# CAN.net
KiCad netlist of a schematic drawn in Altium Designer
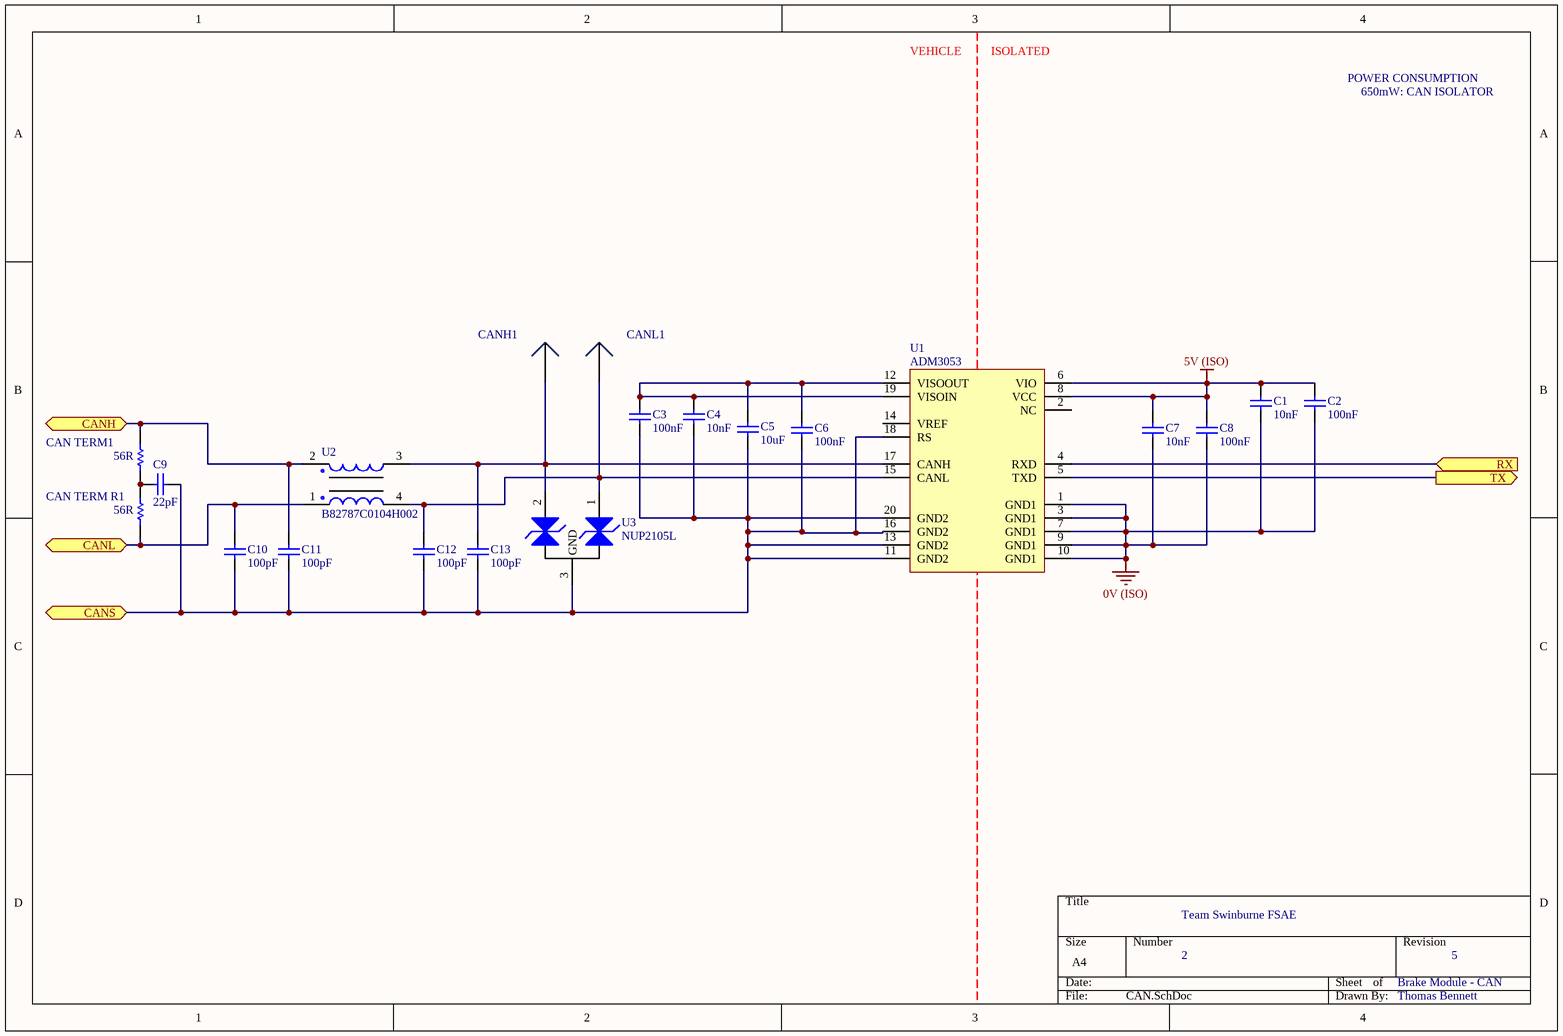
[diagram p0: CAN.SchDoc]

(export (version "E")
  (design (tool "Eeschema 10.0.6"))
  (components
    (comp (ref "C1")
      (value "10nF")
      (footprint "C0603")
      (fields (field (name "PART NUMBER") "CC0603JPX7R9BB103") (field (name "TOLERANCE") "5%"))
      (libsource (lib "AMS_Component_Library") (part "Capacitor"))
    )
    (comp (ref "C2")
      (value "100nF")
      (footprint "C0603")
      (fields (field (name "PART NUMBER") "CC0603ZPY5V9BB104") (field (name "TOLERANCE") "5%"))
      (libsource (lib "AMS_Component_Library") (part "Capacitor"))
    )
    (comp (ref "C3")
      (value "100nF")
      (footprint "C0603")
      (fields (field (name "PART NUMBER") "CC0603ZPY5V9BB104") (field (name "TOLERANCE") "5%"))
      (libsource (lib "AMS_Component_Library") (part "Capacitor"))
    )
    (comp (ref "C4")
      (value "10nF")
      (footprint "C0603")
      (fields (field (name "PART NUMBER") "CC0603JPX7R9BB103") (field (name "TOLERANCE") "5%"))
      (libsource (lib "AMS_Component_Library") (part "Capacitor"))
    )
    (comp (ref "C5")
      (value "10uF")
      (footprint "C0603")
      (fields (field (name "PART NUMBER") "GRM188R6YA106MA73D") (field (name "TOLERANCE") "20%"))
      (libsource (lib "AMS_Component_Library") (part "Capacitor"))
    )
    (comp (ref "C6")
      (value "100nF")
      (footprint "C0603")
      (fields (field (name "PART NUMBER") "CC0603ZPY5V9BB104") (field (name "TOLERANCE") "5%"))
      (libsource (lib "AMS_Component_Library") (part "Capacitor"))
    )
    (comp (ref "C7")
      (value "10nF")
      (footprint "C0603")
      (fields (field (name "PART NUMBER") "CC0603JPX7R9BB103") (field (name "TOLERANCE") "5%"))
      (libsource (lib "AMS_Component_Library") (part "Capacitor"))
    )
    (comp (ref "C8")
      (value "100nF")
      (footprint "C0603")
      (fields (field (name "PART NUMBER") "CC0603ZPY5V9BB104") (field (name "TOLERANCE") "5%"))
      (libsource (lib "AMS_Component_Library") (part "Capacitor"))
    )
    (comp (ref "C9")
      (value "22pF")
      (footprint "0805")
      (fields
        (field (name "PART NUMBER") "GRM21A5C2E220JW01D")
        (field (name "TOLERANCE") "±5%")
        (field (name "MANUFACTURER") "muRata")
      )
      (libsource (lib "ts_20-standard-library") (part "Capacitor"))
    )
    (comp (ref "C10")
      (value "100pF")
      (footprint "C0603")
      (fields (field (name "PART NUMBER") "CC0603JPNPO9BN101") (field (name "TOLERANCE") "5%"))
      (libsource (lib "AMS_Component_Library") (part "Capacitor"))
    )
    (comp (ref "C11")
      (value "100pF")
      (footprint "C0603")
      (fields (field (name "PART NUMBER") "CC0603JPNPO9BN101") (field (name "TOLERANCE") "5%"))
      (libsource (lib "AMS_Component_Library") (part "Capacitor"))
    )
    (comp (ref "C12")
      (value "100pF")
      (footprint "C0603")
      (fields (field (name "PART NUMBER") "CC0603JPNPO9BN101") (field (name "TOLERANCE") "5%"))
      (libsource (lib "AMS_Component_Library") (part "Capacitor"))
    )
    (comp (ref "C13")
      (value "100pF")
      (footprint "C0603")
      (fields (field (name "PART NUMBER") "CC0603JPNPO9BN101") (field (name "TOLERANCE") "5%"))
      (libsource (lib "AMS_Component_Library") (part "Capacitor"))
    )
    (comp (ref "CAN TERM R1")
      (value "56R")
      (footprint "0805")
      (fields
        (field (name "PART NUMBER") "RC0805FR0756RL")
        (field (name "MANUFACTURER") "YAGEO")
        (field (name "TOLERANCE") "0.01")
      )
      (libsource (lib "ts_20-standard-library") (part "Resistor"))
    )
    (comp (ref "CAN TERM1")
      (value "56R")
      (footprint "0805")
      (fields
        (field (name "PART NUMBER") "RC0805FR0756RL")
        (field (name "MANUFACTURER") "YAGEO")
        (field (name "TOLERANCE") "0.01")
      )
      (libsource (lib "ts_20-standard-library") (part "Resistor"))
    )
    (comp (ref "CANH1")
      (value "0mm")
      (footprint "SMD Test Point")
      (fields (field (name "PART NUMBER") "SMD Test Point") (field (name "CONTACT") "NA"))
      (libsource (lib "ts_20-standard-connectors") (part "Test Point"))
    )
    (comp (ref "CANL1")
      (value "0mm")
      (footprint "SMD Test Point")
      (fields (field (name "PART NUMBER") "SMD Test Point") (field (name "CONTACT") "NA"))
      (libsource (lib "ts_20-standard-connectors") (part "Test Point"))
    )
    (comp (ref "U1")
      (value "ADM3053")
      (footprint "AD SOIC-W 20")
      (description "Isolated CAN Transceiver")
      (fields
        (field (name "MANUFACTURER") "Analogue Devices")
        (field (name "DIGIKEY PART NUMBER") "ADM3053BRWZ-ND")
      )
      (libsource (lib "ts_20-standard-library") (part "ADM3053"))
    )
    (comp (ref "U2")
      (value "B82787C0104H002")
      (footprint "TDK 4-PC Pad")
      (description "100µH @ 100kHz 2 Line Common Mode Choke Surface Mount 5.8 kOhms @ 10MHz 150mA DCR 2Ohm")
      (fields
        (field (name "MANUFACTURER") "EPCOS (TDK)")
        (field (name "DIGIKEY PART NUMBER") "495-4598-1-ND")
      )
      (libsource (lib "ts_20-standard-library") (part "B82787C0104H002"))
    )
    (comp (ref "U3")
      (value "NUP2105L")
      (footprint "ON SOT-23")
      (description "Dual Line CAN Bus Protector")
      (fields
        (field (name "MANUFACTURER") "ON Semiconductor")
        (field (name "DIGIKEY PART NUMBER") "NUP2105LT1GOSCT-ND")
      )
      (libsource (lib "ts_20-standard-library") (part "NUP2105L"))
    )
  )
  (nets
    (net (code "1") (name "/CANH") (class "Default")
      (node (ref "C11") (pin "2") (pinfunction "2_2") (pintype "passive"))
      (node (ref "CAN TERM1") (pin "2") (pinfunction "2_2") (pintype "passive"))
      (node (ref "U2") (pin "2") (pinfunction "2_2") (pintype "passive"))
    )
    (net (code "2") (name "/CANL") (class "Default")
      (node (ref "C10") (pin "2") (pinfunction "2_2") (pintype "passive"))
      (node (ref "CAN TERM R1") (pin "1") (pinfunction "1_1") (pintype "passive"))
      (node (ref "U2") (pin "1") (pinfunction "1_1") (pintype "passive"))
    )
    (net (code "3") (name "/CANS") (class "Default")
      (node (ref "C10") (pin "1") (pinfunction "1_1") (pintype "passive"))
      (node (ref "C11") (pin "1") (pinfunction "1_1") (pintype "passive"))
      (node (ref "C12") (pin "1") (pinfunction "1_1") (pintype "passive"))
      (node (ref "C13") (pin "1") (pinfunction "1_1") (pintype "passive"))
      (node (ref "C3") (pin "1") (pinfunction "1_1") (pintype "passive"))
      (node (ref "C4") (pin "1") (pinfunction "1_1") (pintype "passive"))
      (node (ref "C5") (pin "1") (pinfunction "1_1") (pintype "passive"))
      (node (ref "C6") (pin "1") (pinfunction "1_1") (pintype "passive"))
      (node (ref "C9") (pin "2") (pinfunction "2_2") (pintype "passive"))
      (node (ref "U1") (pin "11") (pinfunction "GND2_11") (pintype "passive"))
      (node (ref "U1") (pin "13") (pinfunction "GND2_13") (pintype "passive"))
      (node (ref "U1") (pin "16") (pinfunction "GND2_16") (pintype "passive"))
      (node (ref "U1") (pin "18") (pinfunction "RS_18") (pintype "passive"))
      (node (ref "U1") (pin "20") (pinfunction "GND2_20") (pintype "passive"))
      (node (ref "U3") (pin "3") (pinfunction "GND_3") (pintype "power_in"))
    )
    (net (code "4") (name "/RX") (class "Default")
      (node (ref "U1") (pin "4") (pinfunction "RXD_4") (pintype "passive"))
    )
    (net (code "5") (name "/TX") (class "Default")
      (node (ref "U1") (pin "5") (pinfunction "TXD_5") (pintype "passive"))
    )
    (net (code "6") (name "0V (ISO)") (class "Default")
      (node (ref "C1") (pin "1") (pinfunction "1_1") (pintype "passive"))
      (node (ref "C2") (pin "1") (pinfunction "1_1") (pintype "passive"))
      (node (ref "C7") (pin "1") (pinfunction "1_1") (pintype "passive"))
      (node (ref "C8") (pin "1") (pinfunction "1_1") (pintype "passive"))
      (node (ref "U1") (pin "1") (pinfunction "GND1_1") (pintype "passive"))
      (node (ref "U1") (pin "10") (pinfunction "GND1_10") (pintype "passive"))
      (node (ref "U1") (pin "3") (pinfunction "GND1_3") (pintype "passive"))
      (node (ref "U1") (pin "7") (pinfunction "GND1_7") (pintype "passive"))
      (node (ref "U1") (pin "9") (pinfunction "GND1_9") (pintype "passive"))
    )
    (net (code "7") (name "5V (ISO)") (class "Default")
      (node (ref "C1") (pin "2") (pinfunction "2_2") (pintype "passive"))
      (node (ref "C2") (pin "2") (pinfunction "2_2") (pintype "passive"))
      (node (ref "C7") (pin "2") (pinfunction "2_2") (pintype "passive"))
      (node (ref "C8") (pin "2") (pinfunction "2_2") (pintype "passive"))
      (node (ref "U1") (pin "6") (pinfunction "VIO_6") (pintype "passive"))
      (node (ref "U1") (pin "8") (pinfunction "VCC_8") (pintype "passive"))
    )
    (net (code "8") (name "Net-(C9-Pad1)") (class "Default")
      (node (ref "C9") (pin "1") (pinfunction "1_1") (pintype "passive"))
      (node (ref "CAN TERM R1") (pin "2") (pinfunction "2_2") (pintype "passive"))
      (node (ref "CAN TERM1") (pin "1") (pinfunction "1_1") (pintype "passive"))
    )
    (net (code "9") (name "Net-(U1-CANH)") (class "Default")
      (node (ref "C13") (pin "2") (pinfunction "2_2") (pintype "passive"))
      (node (ref "CANH1") (pin "1") (pinfunction "1_1") (pintype "passive"))
      (node (ref "U1") (pin "17") (pinfunction "CANH_17") (pintype "passive"))
      (node (ref "U2") (pin "3") (pinfunction "3_3") (pintype "power_in"))
      (node (ref "U3") (pin "2") (pinfunction "CAN_L_2") (pintype "passive"))
    )
    (net (code "10") (name "Net-(U1-CANL)") (class "Default")
      (node (ref "C12") (pin "2") (pinfunction "2_2") (pintype "passive"))
      (node (ref "CANL1") (pin "1") (pinfunction "1_1") (pintype "passive"))
      (node (ref "U1") (pin "15") (pinfunction "CANL_15") (pintype "passive"))
      (node (ref "U2") (pin "4") (pinfunction "4_4") (pintype "passive"))
      (node (ref "U3") (pin "1") (pinfunction "CAN_H_1") (pintype "passive"))
    )
    (net (code "11") (name "Net-(U1-VISOIN)") (class "Default")
      (node (ref "C3") (pin "2") (pinfunction "2_2") (pintype "passive"))
      (node (ref "C4") (pin "2") (pinfunction "2_2") (pintype "passive"))
      (node (ref "C5") (pin "2") (pinfunction "2_2") (pintype "passive"))
      (node (ref "C6") (pin "2") (pinfunction "2_2") (pintype "passive"))
      (node (ref "U1") (pin "12") (pinfunction "VISOOUT_12") (pintype "passive"))
      (node (ref "U1") (pin "19") (pinfunction "VISOIN_19") (pintype "passive"))
    )
    (net (code "12") (name "unconnected-(U1-NC-Pad2)") (class "Default")
      (node (ref "U1") (pin "2") (pinfunction "NC_2") (pintype "passive"))
    )
    (net (code "13") (name "unconnected-(U1-VREF-Pad14)") (class "Default")
      (node (ref "U1") (pin "14") (pinfunction "VREF_14") (pintype "passive"))
    )
  )
)
